# controller11.net
KiCad netlist of a schematic drawn in EAGLE
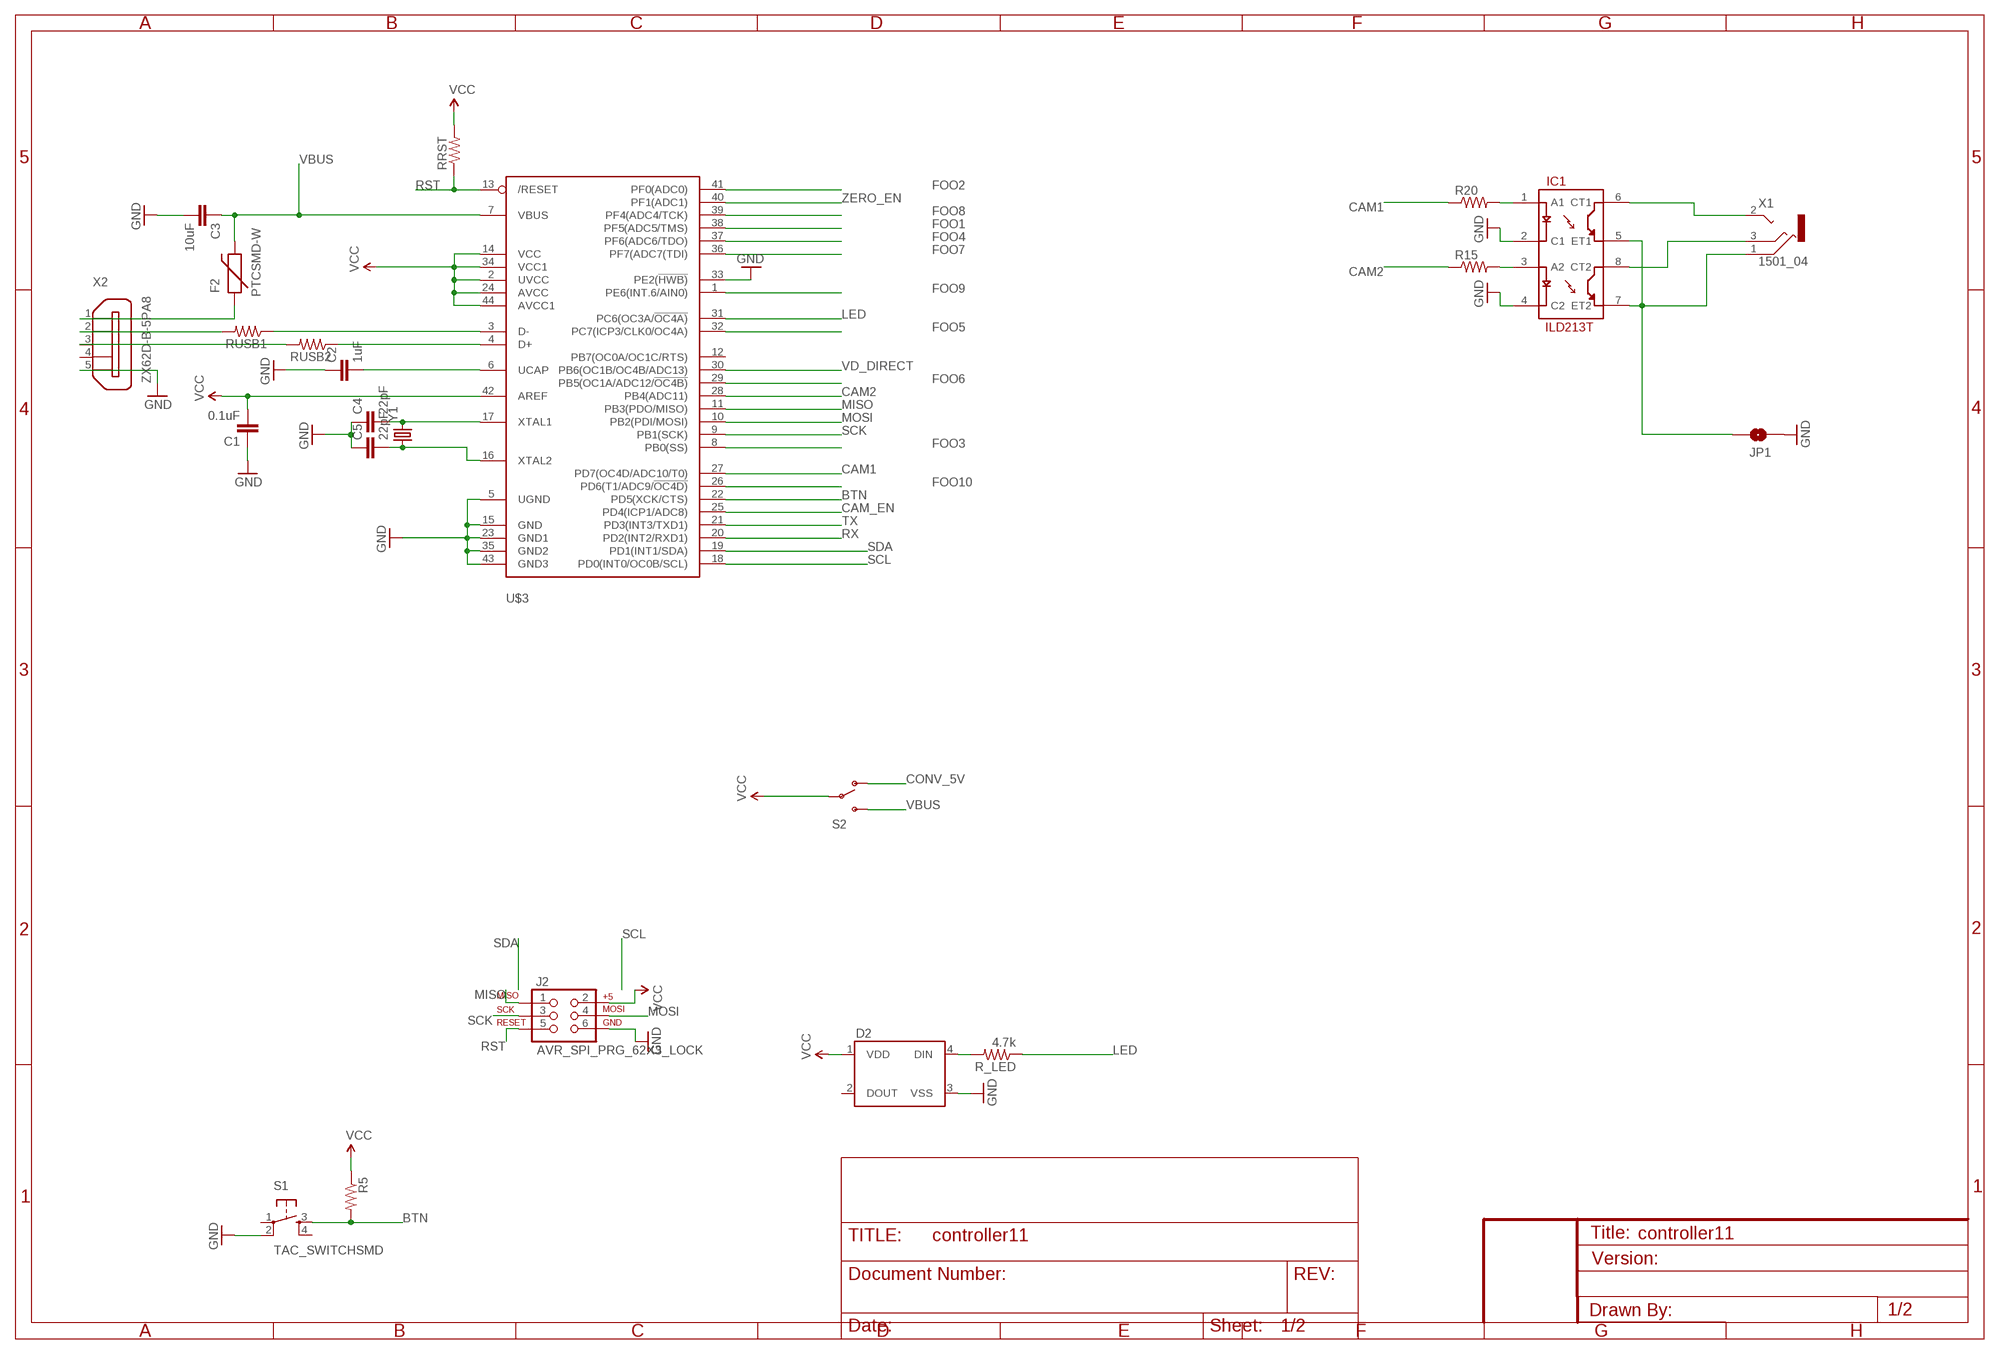
[diagram p0: schematic, sheet 1]
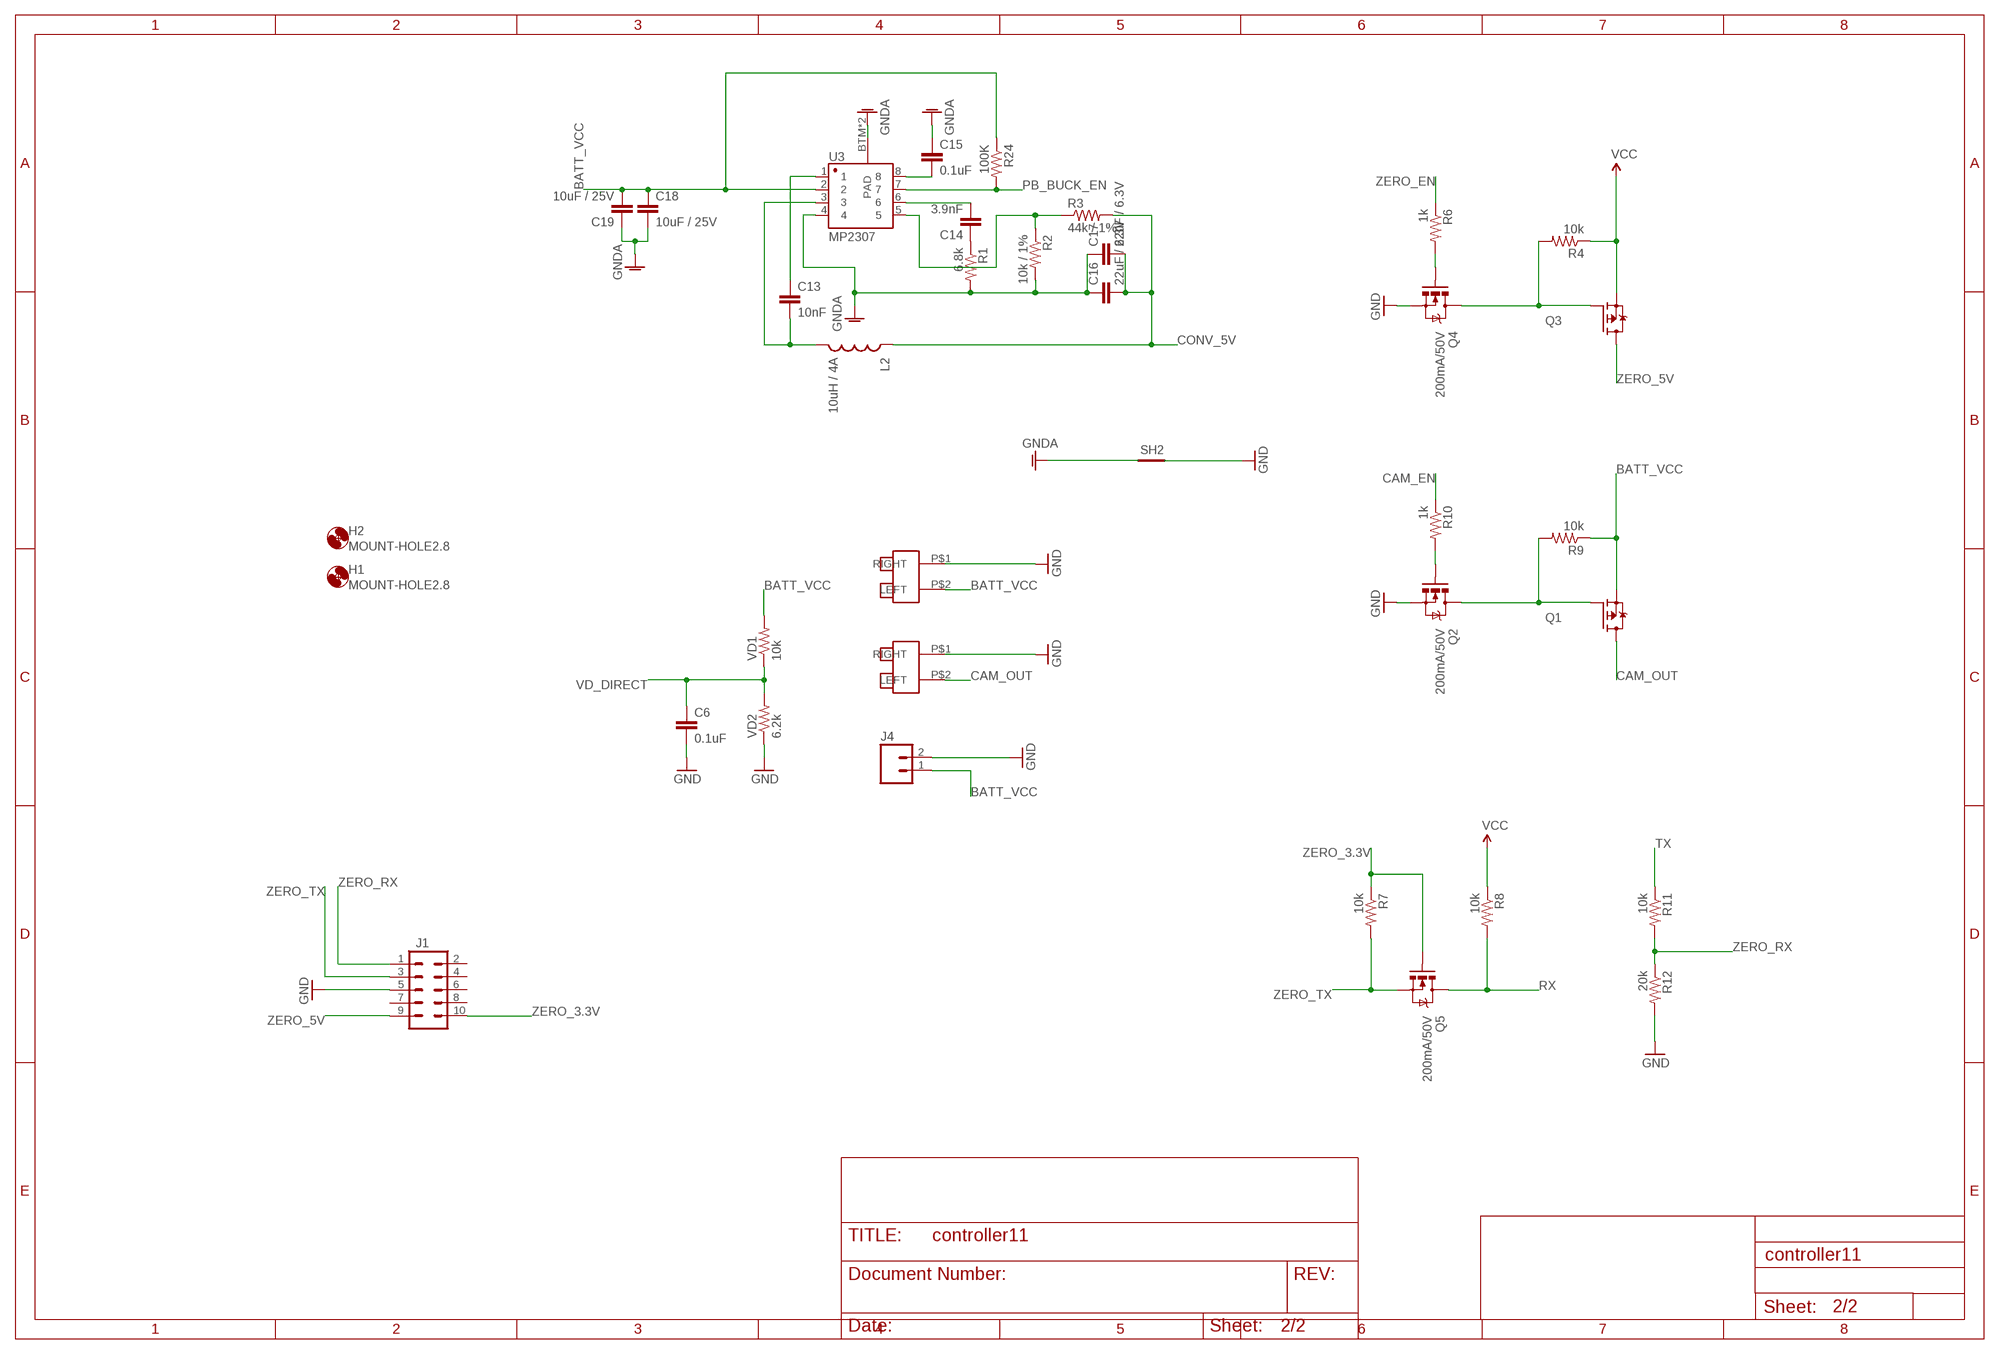
[diagram p1: schematic, sheet 2]

(export (version "E")
  (design (tool "Eeschema 10.0.6"))
  (components
    (comp (ref "C1")
      (value "0.1uF")
      (footprint "eagle-import:1206")
      (libsource (lib "eagle-import") (part "CAP1206"))
    )
    (comp (ref "C2")
      (value "1uF")
      (footprint "eagle-import:1206")
      (libsource (lib "eagle-import") (part "CAP1206"))
    )
    (comp (ref "C3")
      (value "10uF")
      (footprint "eagle-import:1206")
      (libsource (lib "eagle-import") (part "SparkFun-Passives_CAP1206"))
    )
    (comp (ref "C4")
      (value "22pF")
      (footprint "eagle-import:1206")
      (libsource (lib "eagle-import") (part "SparkFun-Passives_CAP1206"))
    )
    (comp (ref "C5")
      (value "22pF")
      (footprint "eagle-import:1206")
      (libsource (lib "eagle-import") (part "SparkFun-Passives_CAP1206"))
    )
    (comp (ref "D2")
      (value "WS2812B")
      (footprint "eagle-import:WS2812B")
      (libsource (lib "eagle-import") (part "WS2812B"))
    )
    (comp (ref "F2")
      (value "PTCSMD-W")
      (footprint "eagle-import:PTC-1206-WIDE")
      (libsource (lib "eagle-import") (part "PTCSMD-W"))
    )
    (comp (ref "IC1")
      (value "ILD213T")
      (footprint "eagle-import:SO08")
      (libsource (lib "eagle-import") (part "ILD213T"))
    )
    (comp (ref "J2")
      (value "AVR_SPI_PRG_62X3_LOCK")
      (footprint "eagle-import:2X3_LOCK")
      (libsource (lib "eagle-import") (part "AVR_SPI_PRG_62X3_LOCK"))
    )
    (comp (ref "JP1")
      (value "JUMPER-PAD-2-NOYES_SILK")
      (footprint "eagle-import:PAD-JUMPER-2-NO_YES_SILK")
      (libsource (lib "eagle-import") (part "JUMPER-PAD-2-NOYES_SILK"))
    )
    (comp (ref "R5")
      (value "RESISTOR1206")
      (footprint "eagle-import:1206")
      (libsource (lib "eagle-import") (part "RESISTOR1206"))
    )
    (comp (ref "R15")
      (value "RESISTOR1206")
      (footprint "eagle-import:1206")
      (libsource (lib "eagle-import") (part "RESISTOR1206"))
    )
    (comp (ref "R20")
      (value "RESISTOR1206")
      (footprint "eagle-import:1206")
      (libsource (lib "eagle-import") (part "RESISTOR1206"))
    )
    (comp (ref "RRST")
      (value "RESISTOR1206")
      (footprint "eagle-import:1206")
      (libsource (lib "eagle-import") (part "RESISTOR1206"))
    )
    (comp (ref "RUSB1")
      (value "RESISTOR1206")
      (footprint "eagle-import:1206")
      (libsource (lib "eagle-import") (part "RESISTOR1206"))
    )
    (comp (ref "RUSB2")
      (value "RESISTOR1206")
      (footprint "eagle-import:1206")
      (libsource (lib "eagle-import") (part "RESISTOR1206"))
    )
    (comp (ref "R_LED")
      (value "4.7k")
      (footprint "eagle-import:1206")
      (libsource (lib "eagle-import") (part "SparkFun-Resistors_RESISTOR1206"))
    )
    (comp (ref "S1")
      (value "TAC_SWITCHSMD")
      (footprint "eagle-import:TACTILE-SWITCH-SMD")
      (libsource (lib "eagle-import") (part "TAC_SWITCHSMD"))
    )
    (comp (ref "S2")
      (value "SWITCH-SPDTSMD2")
      (footprint "eagle-import:SWITCH-SPDT-SMD")
      (libsource (lib "eagle-import") (part "SWITCH-SPDTSMD2"))
    )
    (comp (ref "U$3")
      (value "ATMEGA32U4-AU")
      (footprint "eagle-import:TQFP44")
      (libsource (lib "eagle-import") (part "ATMEGA32U4-AU"))
    )
    (comp (ref "X1")
      (value "1501_04")
      (footprint "eagle-import:1501_05")
      (libsource (lib "eagle-import") (part "1501_04"))
    )
    (comp (ref "X2")
      (value "ZX62D-B-5PA8")
      (footprint "eagle-import:ZX62D-B-5PA8")
      (fields (field (name "MF") "Hirose"))
      (libsource (lib "eagle-import") (part "ZX62D-B-5PA8"))
    )
    (comp (ref "Y1")
      (value "CRYSTALCRYSTAL-SMD-5X3-16MHZ")
      (footprint "eagle-import:CRYSTAL-SMD-5X3")
      (libsource (lib "eagle-import") (part "CRYSTALCRYSTAL-SMD-5X3-16MHZ"))
    )
    (comp (ref "C6")
      (value "0.1uF")
      (footprint "eagle-import:1206")
      (libsource (lib "eagle-import") (part "CAP1206"))
    )
    (comp (ref "C13")
      (value "10nF")
      (footprint "eagle-import:1206")
      (libsource (lib "eagle-import") (part "CAP1206"))
    )
    (comp (ref "C14")
      (value "3.9nF")
      (footprint "eagle-import:1206")
      (libsource (lib "eagle-import") (part "CAP1206"))
    )
    (comp (ref "C15")
      (value "0.1uF")
      (footprint "eagle-import:1206")
      (libsource (lib "eagle-import") (part "CAP1206"))
    )
    (comp (ref "C16")
      (value "22uF / 6.3V")
      (footprint "eagle-import:1210")
      (libsource (lib "eagle-import") (part "CAP1210"))
    )
    (comp (ref "C17")
      (value "22uF / 6.3V")
      (footprint "eagle-import:1210")
      (libsource (lib "eagle-import") (part "CAP1210"))
    )
    (comp (ref "C18")
      (value "10uF / 25V")
      (footprint "eagle-import:1210")
      (libsource (lib "eagle-import") (part "CAP1210"))
    )
    (comp (ref "C19")
      (value "10uF / 25V")
      (footprint "eagle-import:1210")
      (libsource (lib "eagle-import") (part "CAP1210"))
    )
    (comp (ref "H1")
      (value "MOUNT-HOLE2.8")
      (footprint "eagle-import:2,8")
      (libsource (lib "eagle-import") (part "MOUNT-HOLE2.8"))
    )
    (comp (ref "H2")
      (value "MOUNT-HOLE2.8")
      (footprint "eagle-import:2,8")
      (libsource (lib "eagle-import") (part "MOUNT-HOLE2.8"))
    )
    (comp (ref "J1")
      (value "M05X2PTH")
      (footprint "eagle-import:AVR_ICSP")
      (libsource (lib "eagle-import") (part "M05X2PTH"))
    )
    (comp (ref "J4")
      (value "M02LOCK")
      (footprint "eagle-import:1X02_LOCK")
      (libsource (lib "eagle-import") (part "M02LOCK"))
    )
    (comp (ref "L2")
      (value "10uH / 4A")
      (footprint "eagle-import:SRU1038")
      (libsource (lib "eagle-import") (part "INDUCTORSRU1038"))
    )
    (comp (ref "Q1")
      (value "FDD4141TO252")
      (footprint "eagle-import:TO252")
      (libsource (lib "eagle-import") (part "FDD4141TO252"))
    )
    (comp (ref "Q2")
      (value "200mA/50V")
      (footprint "eagle-import:SOT23-3")
      (libsource (lib "eagle-import") (part "MOSFET-NCHANNELBSS138"))
    )
    (comp (ref "Q3")
      (value "FDD4141TO252")
      (footprint "eagle-import:TO252")
      (libsource (lib "eagle-import") (part "FDD4141TO252"))
    )
    (comp (ref "Q4")
      (value "200mA/50V")
      (footprint "eagle-import:SOT23-3")
      (libsource (lib "eagle-import") (part "MOSFET-NCHANNELBSS138"))
    )
    (comp (ref "Q5")
      (value "200mA/50V")
      (footprint "eagle-import:SOT23-3")
      (libsource (lib "eagle-import") (part "MOSFET-NCHANNELBSS138"))
    )
    (comp (ref "R1")
      (value "6.8k")
      (footprint "eagle-import:1206")
      (libsource (lib "eagle-import") (part "SparkFun-Resistors_RESISTOR1206"))
    )
    (comp (ref "R2")
      (value "10k / 1%")
      (footprint "eagle-import:1206")
      (libsource (lib "eagle-import") (part "SparkFun-Resistors_RESISTOR1206"))
    )
    (comp (ref "R3")
      (value "44k / 1%")
      (footprint "eagle-import:1206")
      (libsource (lib "eagle-import") (part "SparkFun-Resistors_RESISTOR1206"))
    )
    (comp (ref "R4")
      (value "10k")
      (footprint "eagle-import:1206")
      (libsource (lib "eagle-import") (part "SparkFun-Resistors_RESISTOR1206"))
    )
    (comp (ref "R6")
      (value "1k")
      (footprint "eagle-import:1206")
      (libsource (lib "eagle-import") (part "SparkFun-Resistors_RESISTOR1206"))
    )
    (comp (ref "R7")
      (value "10k")
      (footprint "eagle-import:1206")
      (libsource (lib "eagle-import") (part "SparkFun-Resistors_RESISTOR1206"))
    )
    (comp (ref "R8")
      (value "10k")
      (footprint "eagle-import:1206")
      (libsource (lib "eagle-import") (part "SparkFun-Resistors_RESISTOR1206"))
    )
    (comp (ref "R9")
      (value "10k")
      (footprint "eagle-import:1206")
      (libsource (lib "eagle-import") (part "SparkFun-Resistors_RESISTOR1206"))
    )
    (comp (ref "R10")
      (value "1k")
      (footprint "eagle-import:1206")
      (libsource (lib "eagle-import") (part "SparkFun-Resistors_RESISTOR1206"))
    )
    (comp (ref "R11")
      (value "10k")
      (footprint "eagle-import:1206")
      (libsource (lib "eagle-import") (part "SparkFun-Resistors_RESISTOR1206"))
    )
    (comp (ref "R12")
      (value "20k")
      (footprint "eagle-import:1206")
      (libsource (lib "eagle-import") (part "SparkFun-Resistors_RESISTOR1206"))
    )
    (comp (ref "R24")
      (value "100K")
      (footprint "eagle-import:1206")
      (libsource (lib "eagle-import") (part "SparkFun-Resistors_RESISTOR1206"))
    )
    (comp (ref "SH2")
      (value "SHORT-HT5")
      (footprint "eagle-import:SHORT_TOP-50")
      (libsource (lib "eagle-import") (part "SHORT-HT5"))
    )
    (comp (ref "U$4")
      (value "NANOFIT2")
      (footprint "eagle-import:NANOFIT2")
      (libsource (lib "eagle-import") (part "NANOFIT2"))
    )
    (comp (ref "U$5")
      (value "NANOFIT2")
      (footprint "eagle-import:NANOFIT2")
      (libsource (lib "eagle-import") (part "NANOFIT2"))
    )
    (comp (ref "U3")
      (value "MP2307")
      (footprint "eagle-import:SO08")
      (libsource (lib "eagle-import") (part "GENERIC-SOIC8MSGEQ7N-FILTER"))
    )
    (comp (ref "VD1")
      (value "10k")
      (footprint "eagle-import:1206")
      (libsource (lib "eagle-import") (part "RESISTOR1206"))
    )
    (comp (ref "VD2")
      (value "6.2k")
      (footprint "eagle-import:1206")
      (libsource (lib "eagle-import") (part "RESISTOR1206"))
    )
  )
  (nets
    (net (code "1") (name "BATT_VCC") (class "Default")
      (node (ref "C18") (pin "1") (pinfunction "1_1") (pintype "passive"))
      (node (ref "C19") (pin "2") (pinfunction "2_2") (pintype "passive"))
      (node (ref "J4") (pin "1") (pinfunction "1_1") (pintype "passive"))
      (node (ref "Q1") (pin "2") (pinfunction "S_2") (pintype "passive"))
      (node (ref "R24") (pin "1") (pinfunction "1_1") (pintype "passive"))
      (node (ref "R9") (pin "1") (pinfunction "1_1") (pintype "passive"))
      (node (ref "U$4") (pin "P$2") (pinfunction "LEFT_P$2") (pintype "bidirectional"))
      (node (ref "U3") (pin "2") (pinfunction "2_2") (pintype "bidirectional"))
      (node (ref "VD1") (pin "2") (pinfunction "2_2") (pintype "passive"))
    )
    (net (code "2") (name "BTN") (class "Default")
      (node (ref "R5") (pin "2") (pinfunction "2_2") (pintype "passive"))
      (node (ref "S1") (pin "3") (pinfunction "3_3") (pintype "passive"))
      (node (ref "U$3") (pin "22") (pinfunction "PD5(XCK/CTS)_22") (pintype "bidirectional"))
    )
    (net (code "3") (name "CAM1") (class "Default")
      (node (ref "R20") (pin "1") (pinfunction "1_1") (pintype "passive"))
      (node (ref "U$3") (pin "27") (pinfunction "PD7(OC4D/ADC10/T0)_27") (pintype "bidirectional"))
    )
    (net (code "4") (name "CAM2") (class "Default")
      (node (ref "R15") (pin "1") (pinfunction "1_1") (pintype "passive"))
      (node (ref "U$3") (pin "28") (pinfunction "PB4(ADC11)_28") (pintype "bidirectional"))
    )
    (net (code "5") (name "CAM_EN") (class "Default")
      (node (ref "R10") (pin "1") (pinfunction "1_1") (pintype "passive"))
      (node (ref "U$3") (pin "25") (pinfunction "PD4(ICP1/ADC8)_25") (pintype "bidirectional"))
    )
    (net (code "6") (name "CAM_OUT") (class "Default")
      (node (ref "Q1") (pin "3") (pinfunction "D_3") (pintype "passive"))
      (node (ref "U$5") (pin "P$2") (pinfunction "LEFT_P$2") (pintype "bidirectional"))
    )
    (net (code "7") (name "CONV_5V") (class "Default")
      (node (ref "C16") (pin "2") (pinfunction "2_2") (pintype "passive"))
      (node (ref "C17") (pin "2") (pinfunction "2_2") (pintype "passive"))
      (node (ref "L2") (pin "1") (pinfunction "1_1") (pintype "passive"))
      (node (ref "R3") (pin "2") (pinfunction "2_2") (pintype "passive"))
      (node (ref "S2") (pin "1") (pinfunction "O_1") (pintype "passive"))
    )
    (net (code "8") (name "FOO1") (class "Default")
      (node (ref "U$3") (pin "38") (pinfunction "PF5(ADC5/TMS)_38") (pintype "bidirectional"))
    )
    (net (code "9") (name "FOO2") (class "Default")
      (node (ref "U$3") (pin "41") (pinfunction "PF0(ADC0)_41") (pintype "bidirectional"))
    )
    (net (code "10") (name "FOO3") (class "Default")
      (node (ref "U$3") (pin "8") (pinfunction "PB0(SS)_8") (pintype "bidirectional"))
    )
    (net (code "11") (name "FOO4") (class "Default")
      (node (ref "U$3") (pin "37") (pinfunction "PF6(ADC6/TDO)_37") (pintype "bidirectional"))
    )
    (net (code "12") (name "FOO5") (class "Default")
      (node (ref "U$3") (pin "32") (pinfunction "PC7(ICP3/CLK0/OC4A)_32") (pintype "bidirectional"))
    )
    (net (code "13") (name "FOO6") (class "Default")
      (node (ref "U$3") (pin "29") (pinfunction "PB5(OC1A/ADC12/~{OC4B})_29") (pintype "bidirectional"))
    )
    (net (code "14") (name "FOO7") (class "Default")
      (node (ref "U$3") (pin "36") (pinfunction "PF7(ADC7(TDI)_36") (pintype "bidirectional"))
    )
    (net (code "15") (name "FOO8") (class "Default")
      (node (ref "U$3") (pin "39") (pinfunction "PF4(ADC4/TCK)_39") (pintype "bidirectional"))
    )
    (net (code "16") (name "FOO9") (class "Default")
      (node (ref "U$3") (pin "1") (pinfunction "PE6(INT.6/AIN0)_1") (pintype "bidirectional"))
    )
    (net (code "17") (name "FOO10") (class "Default")
      (node (ref "U$3") (pin "26") (pinfunction "PD6(T1/ADC9/~{OC4D})_26") (pintype "bidirectional"))
    )
    (net (code "18") (name "GND") (class "Default")
      (node (ref "C1") (pin "1") (pinfunction "1_1") (pintype "passive"))
      (node (ref "C2") (pin "1") (pinfunction "1_1") (pintype "passive"))
      (node (ref "C3") (pin "2") (pinfunction "2_2") (pintype "passive"))
      (node (ref "C4") (pin "1") (pinfunction "1_1") (pintype "passive"))
      (node (ref "C5") (pin "1") (pinfunction "1_1") (pintype "passive"))
      (node (ref "C6") (pin "2") (pinfunction "2_2") (pintype "passive"))
      (node (ref "D2") (pin "3") (pinfunction "VSS_3") (pintype "power_in"))
      (node (ref "IC1") (pin "2") (pinfunction "C1_2") (pintype "bidirectional"))
      (node (ref "IC1") (pin "4") (pinfunction "C2_4") (pintype "bidirectional"))
      (node (ref "J1") (pin "5") (pinfunction "5_5") (pintype "passive"))
      (node (ref "J2") (pin "6") (pinfunction "6_6") (pintype "passive"))
      (node (ref "J4") (pin "2") (pinfunction "2_2") (pintype "passive"))
      (node (ref "JP1") (pin "1") (pinfunction "1_1") (pintype "passive"))
      (node (ref "Q2") (pin "2") (pinfunction "S_2") (pintype "passive"))
      (node (ref "Q4") (pin "2") (pinfunction "S_2") (pintype "passive"))
      (node (ref "R12") (pin "2") (pinfunction "2_2") (pintype "passive"))
      (node (ref "S1") (pin "2") (pinfunction "2_2") (pintype "passive"))
      (node (ref "SH2") (pin "2") (pinfunction "P$2_2") (pintype "bidirectional"))
      (node (ref "U$3") (pin "15") (pinfunction "GND_15") (pintype "bidirectional"))
      (node (ref "U$3") (pin "23") (pinfunction "GND1_23") (pintype "bidirectional"))
      (node (ref "U$3") (pin "33") (pinfunction "PE2(~{HWB})_33") (pintype "bidirectional"))
      (node (ref "U$3") (pin "35") (pinfunction "GND2_35") (pintype "bidirectional"))
      (node (ref "U$3") (pin "43") (pinfunction "GND3_43") (pintype "bidirectional"))
      (node (ref "U$3") (pin "5") (pinfunction "UGND_5") (pintype "bidirectional"))
      (node (ref "U$4") (pin "P$1") (pinfunction "RIGHT_P$1") (pintype "bidirectional"))
      (node (ref "U$5") (pin "P$1") (pinfunction "RIGHT_P$1") (pintype "bidirectional"))
      (node (ref "VD2") (pin "1") (pinfunction "1_1") (pintype "passive"))
      (node (ref "X2") (pin "5") (pinfunction "5_5") (pintype "passive"))
    )
    (net (code "19") (name "GNDA") (class "Default")
      (node (ref "C15") (pin "1") (pinfunction "1_1") (pintype "passive"))
      (node (ref "C16") (pin "1") (pinfunction "1_1") (pintype "passive"))
      (node (ref "C17") (pin "1") (pinfunction "1_1") (pintype "passive"))
      (node (ref "C18") (pin "2") (pinfunction "2_2") (pintype "passive"))
      (node (ref "C19") (pin "1") (pinfunction "1_1") (pintype "passive"))
      (node (ref "R1") (pin "2") (pinfunction "2_2") (pintype "passive"))
      (node (ref "R2") (pin "2") (pinfunction "2_2") (pintype "passive"))
      (node (ref "SH2") (pin "1") (pinfunction "P$1_1") (pintype "bidirectional"))
      (node (ref "U3") (pin "4") (pinfunction "4_4") (pintype "bidirectional"))
      (node (ref "U3") (pin "BTM") (pinfunction "PAD_BTM") (pintype "bidirectional"))
      (node (ref "U3") (pin "P$1") (pinfunction "PAD_P$1") (pintype "bidirectional"))
    )
    (net (code "20") (name "LED") (class "Default")
      (node (ref "R_LED") (pin "1") (pinfunction "1_1") (pintype "passive"))
      (node (ref "U$3") (pin "31") (pinfunction "PC6(OC3A/~{OC4A})_31") (pintype "bidirectional"))
    )
    (net (code "21") (name "MISO") (class "Default")
      (node (ref "J2") (pin "1") (pinfunction "1_1") (pintype "passive"))
      (node (ref "U$3") (pin "11") (pinfunction "PB3(PDO/MISO)_11") (pintype "bidirectional"))
    )
    (net (code "22") (name "MOSI") (class "Default")
      (node (ref "J2") (pin "4") (pinfunction "4_4") (pintype "passive"))
      (node (ref "U$3") (pin "10") (pinfunction "PB2(PDI/MOSI)_10") (pintype "bidirectional"))
    )
    (net (code "23") (name "Net-(C13-Pad1)") (class "Default")
      (node (ref "C13") (pin "1") (pinfunction "1_1") (pintype "passive"))
      (node (ref "U3") (pin "1") (pinfunction "1_1") (pintype "bidirectional"))
    )
    (net (code "24") (name "Net-(C13-Pad2)") (class "Default")
      (node (ref "C13") (pin "2") (pinfunction "2_2") (pintype "passive"))
      (node (ref "L2") (pin "2") (pinfunction "2_2") (pintype "passive"))
      (node (ref "U3") (pin "3") (pinfunction "3_3") (pintype "bidirectional"))
    )
    (net (code "25") (name "Net-(C14-Pad1)") (class "Default")
      (node (ref "C14") (pin "1") (pinfunction "1_1") (pintype "passive"))
      (node (ref "R1") (pin "1") (pinfunction "1_1") (pintype "passive"))
    )
    (net (code "26") (name "Net-(C14-Pad2)") (class "Default")
      (node (ref "C14") (pin "2") (pinfunction "2_2") (pintype "passive"))
      (node (ref "U3") (pin "6") (pinfunction "6_6") (pintype "bidirectional"))
    )
    (net (code "27") (name "Net-(C15-Pad2)") (class "Default")
      (node (ref "C15") (pin "2") (pinfunction "2_2") (pintype "passive"))
      (node (ref "U3") (pin "8") (pinfunction "8_8") (pintype "bidirectional"))
    )
    (net (code "28") (name "Net-(D2-DIN)") (class "Default")
      (node (ref "D2") (pin "4") (pinfunction "DIN_4") (pintype "input"))
      (node (ref "R_LED") (pin "2") (pinfunction "2_2") (pintype "passive"))
    )
    (net (code "29") (name "Net-(F2-Pad1)") (class "Default")
      (node (ref "F2") (pin "1") (pinfunction "1_1") (pintype "bidirectional"))
      (node (ref "X2") (pin "1") (pinfunction "1_1") (pintype "passive"))
    )
    (net (code "30") (name "Net-(IC1-A1)") (class "Default")
      (node (ref "IC1") (pin "1") (pinfunction "A1_1") (pintype "bidirectional"))
      (node (ref "R20") (pin "2") (pinfunction "2_2") (pintype "passive"))
    )
    (net (code "31") (name "Net-(IC1-A2)") (class "Default")
      (node (ref "IC1") (pin "3") (pinfunction "A2_3") (pintype "bidirectional"))
      (node (ref "R15") (pin "2") (pinfunction "2_2") (pintype "passive"))
    )
    (net (code "32") (name "Net-(IC1-CT1)") (class "Default")
      (node (ref "IC1") (pin "6") (pinfunction "CT1_6") (pintype "bidirectional"))
      (node (ref "X1") (pin "2") (pinfunction "2_2") (pintype "passive"))
    )
    (net (code "33") (name "Net-(IC1-CT2)") (class "Default")
      (node (ref "IC1") (pin "8") (pinfunction "CT2_8") (pintype "bidirectional"))
      (node (ref "X1") (pin "3") (pinfunction "3_3") (pintype "passive"))
    )
    (net (code "34") (name "Net-(IC1-ET1)") (class "Default")
      (node (ref "IC1") (pin "5") (pinfunction "ET1_5") (pintype "bidirectional"))
      (node (ref "IC1") (pin "7") (pinfunction "ET2_7") (pintype "bidirectional"))
      (node (ref "JP1") (pin "2") (pinfunction "2_2") (pintype "passive"))
      (node (ref "X1") (pin "1") (pinfunction "1_1") (pintype "passive"))
    )
    (net (code "35") (name "Net-(Q1-G)") (class "Default")
      (node (ref "Q1") (pin "1") (pinfunction "G_1") (pintype "passive"))
      (node (ref "Q2") (pin "3") (pinfunction "D_3") (pintype "passive"))
      (node (ref "R9") (pin "2") (pinfunction "2_2") (pintype "passive"))
    )
    (net (code "36") (name "Net-(Q2-G)") (class "Default")
      (node (ref "Q2") (pin "1") (pinfunction "G_1") (pintype "passive"))
      (node (ref "R10") (pin "2") (pinfunction "2_2") (pintype "passive"))
    )
    (net (code "37") (name "Net-(Q3-G)") (class "Default")
      (node (ref "Q3") (pin "1") (pinfunction "G_1") (pintype "passive"))
      (node (ref "Q4") (pin "3") (pinfunction "D_3") (pintype "passive"))
      (node (ref "R4") (pin "2") (pinfunction "2_2") (pintype "passive"))
    )
    (net (code "38") (name "Net-(Q4-G)") (class "Default")
      (node (ref "Q4") (pin "1") (pinfunction "G_1") (pintype "passive"))
      (node (ref "R6") (pin "2") (pinfunction "2_2") (pintype "passive"))
    )
    (net (code "39") (name "Net-(R2-Pad1)") (class "Default")
      (node (ref "R2") (pin "1") (pinfunction "1_1") (pintype "passive"))
      (node (ref "R3") (pin "1") (pinfunction "1_1") (pintype "passive"))
      (node (ref "U3") (pin "5") (pinfunction "5_5") (pintype "bidirectional"))
    )
    (net (code "40") (name "Net-(RUSB1-Pad2)") (class "Default")
      (node (ref "RUSB1") (pin "2") (pinfunction "2_2") (pintype "passive"))
      (node (ref "X2") (pin "2") (pinfunction "2_2") (pintype "passive"))
    )
    (net (code "41") (name "Net-(RUSB2-Pad2)") (class "Default")
      (node (ref "RUSB2") (pin "2") (pinfunction "2_2") (pintype "passive"))
      (node (ref "X2") (pin "3") (pinfunction "3_3") (pintype "passive"))
    )
    (net (code "42") (name "Net-(U$3-D+)") (class "Default")
      (node (ref "RUSB2") (pin "1") (pinfunction "1_1") (pintype "passive"))
      (node (ref "U$3") (pin "4") (pinfunction "D+_4") (pintype "bidirectional"))
    )
    (net (code "43") (name "Net-(U$3-D-)") (class "Default")
      (node (ref "RUSB1") (pin "1") (pinfunction "1_1") (pintype "passive"))
      (node (ref "U$3") (pin "3") (pinfunction "D-_3") (pintype "bidirectional"))
    )
    (net (code "44") (name "Net-(U$3-UCAP)") (class "Default")
      (node (ref "C2") (pin "2") (pinfunction "2_2") (pintype "passive"))
      (node (ref "U$3") (pin "6") (pinfunction "UCAP_6") (pintype "bidirectional"))
    )
    (net (code "45") (name "Net-(U$3-XTAL1)") (class "Default")
      (node (ref "C4") (pin "2") (pinfunction "2_2") (pintype "passive"))
      (node (ref "U$3") (pin "17") (pinfunction "XTAL1_17") (pintype "bidirectional"))
      (node (ref "Y1") (pin "3") (pinfunction "2_3") (pintype "passive"))
    )
    (net (code "46") (name "Net-(U$3-XTAL2)") (class "Default")
      (node (ref "C5") (pin "2") (pinfunction "2_2") (pintype "passive"))
      (node (ref "U$3") (pin "16") (pinfunction "XTAL2_16") (pintype "bidirectional"))
      (node (ref "Y1") (pin "1") (pinfunction "1_1") (pintype "passive"))
    )
    (net (code "47") (name "PB_BUCK_EN") (class "Default")
      (node (ref "R24") (pin "2") (pinfunction "2_2") (pintype "passive"))
      (node (ref "U3") (pin "7") (pinfunction "7_7") (pintype "bidirectional"))
    )
    (net (code "48") (name "RST") (class "Default")
      (node (ref "J2") (pin "5") (pinfunction "5_5") (pintype "passive"))
      (node (ref "RRST") (pin "1") (pinfunction "1_1") (pintype "passive"))
      (node (ref "U$3") (pin "13") (pinfunction "/RESET_13") (pintype "bidirectional"))
    )
    (net (code "49") (name "RX") (class "Default")
      (node (ref "Q5") (pin "3") (pinfunction "D_3") (pintype "passive"))
      (node (ref "R8") (pin "2") (pinfunction "2_2") (pintype "passive"))
      (node (ref "U$3") (pin "20") (pinfunction "PD2(INT2/RXD1)_20") (pintype "bidirectional"))
    )
    (net (code "50") (name "SCK") (class "Default")
      (node (ref "J2") (pin "3") (pinfunction "3_3") (pintype "passive"))
      (node (ref "U$3") (pin "9") (pinfunction "PB1(SCK)_9") (pintype "bidirectional"))
    )
    (net (code "51") (name "SCL") (class "Default")
      (node (ref "U$3") (pin "18") (pinfunction "PD0(INT0/OC0B/SCL)_18") (pintype "bidirectional"))
    )
    (net (code "52") (name "SDA") (class "Default")
      (node (ref "U$3") (pin "19") (pinfunction "PD1(INT1/SDA)_19") (pintype "bidirectional"))
    )
    (net (code "53") (name "TX") (class "Default")
      (node (ref "R11") (pin "1") (pinfunction "1_1") (pintype "passive"))
      (node (ref "U$3") (pin "21") (pinfunction "PD3(INT3/TXD1)_21") (pintype "bidirectional"))
    )
    (net (code "54") (name "VBUS") (class "Default")
      (node (ref "C3") (pin "1") (pinfunction "1_1") (pintype "passive"))
      (node (ref "F2") (pin "2") (pinfunction "2_2") (pintype "bidirectional"))
      (node (ref "S2") (pin "3") (pinfunction "S_3") (pintype "passive"))
      (node (ref "U$3") (pin "7") (pinfunction "VBUS_7") (pintype "bidirectional"))
    )
    (net (code "55") (name "VCC") (class "Default")
      (node (ref "C1") (pin "2") (pinfunction "2_2") (pintype "passive"))
      (node (ref "D2") (pin "1") (pinfunction "VDD_1") (pintype "power_in"))
      (node (ref "J2") (pin "2") (pinfunction "2_2") (pintype "passive"))
      (node (ref "Q3") (pin "2") (pinfunction "S_2") (pintype "passive"))
      (node (ref "R4") (pin "1") (pinfunction "1_1") (pintype "passive"))
      (node (ref "R5") (pin "1") (pinfunction "1_1") (pintype "passive"))
      (node (ref "R8") (pin "1") (pinfunction "1_1") (pintype "passive"))
      (node (ref "RRST") (pin "2") (pinfunction "2_2") (pintype "passive"))
      (node (ref "S2") (pin "2") (pinfunction "P_2") (pintype "passive"))
      (node (ref "U$3") (pin "14") (pinfunction "VCC_14") (pintype "bidirectional"))
      (node (ref "U$3") (pin "2") (pinfunction "UVCC_2") (pintype "bidirectional"))
      (node (ref "U$3") (pin "24") (pinfunction "AVCC_24") (pintype "bidirectional"))
      (node (ref "U$3") (pin "34") (pinfunction "VCC1_34") (pintype "bidirectional"))
      (node (ref "U$3") (pin "42") (pinfunction "AREF_42") (pintype "bidirectional"))
      (node (ref "U$3") (pin "44") (pinfunction "AVCC1_44") (pintype "bidirectional"))
    )
    (net (code "56") (name "VD_DIRECT") (class "Default")
      (node (ref "C6") (pin "1") (pinfunction "1_1") (pintype "passive"))
      (node (ref "U$3") (pin "30") (pinfunction "PB6(OC1B/OC4B/ADC13)_30") (pintype "bidirectional"))
      (node (ref "VD1") (pin "1") (pinfunction "1_1") (pintype "passive"))
      (node (ref "VD2") (pin "2") (pinfunction "2_2") (pintype "passive"))
    )
    (net (code "57") (name "ZERO_3.3V") (class "Default")
      (node (ref "J1") (pin "10") (pinfunction "10_10") (pintype "passive"))
      (node (ref "Q5") (pin "1") (pinfunction "G_1") (pintype "passive"))
      (node (ref "R7") (pin "1") (pinfunction "1_1") (pintype "passive"))
    )
    (net (code "58") (name "ZERO_5V") (class "Default")
      (node (ref "J1") (pin "9") (pinfunction "9_9") (pintype "passive"))
      (node (ref "Q3") (pin "3") (pinfunction "D_3") (pintype "passive"))
    )
    (net (code "59") (name "ZERO_EN") (class "Default")
      (node (ref "R6") (pin "1") (pinfunction "1_1") (pintype "passive"))
      (node (ref "U$3") (pin "40") (pinfunction "PF1(ADC1)_40") (pintype "bidirectional"))
    )
    (net (code "60") (name "ZERO_RX") (class "Default")
      (node (ref "J1") (pin "1") (pinfunction "1_1") (pintype "passive"))
      (node (ref "R11") (pin "2") (pinfunction "2_2") (pintype "passive"))
      (node (ref "R12") (pin "1") (pinfunction "1_1") (pintype "passive"))
    )
    (net (code "61") (name "ZERO_TX") (class "Default")
      (node (ref "J1") (pin "3") (pinfunction "3_3") (pintype "passive"))
      (node (ref "Q5") (pin "2") (pinfunction "S_2") (pintype "passive"))
      (node (ref "R7") (pin "2") (pinfunction "2_2") (pintype "passive"))
    )
    (net (code "62") (name "unconnected-(D2-DOUT-Pad2)") (class "Default")
      (node (ref "D2") (pin "2") (pinfunction "DOUT_2") (pintype "output"))
    )
    (net (code "63") (name "unconnected-(J1-Pad2)") (class "Default")
      (node (ref "J1") (pin "2") (pinfunction "2_2") (pintype "passive"))
    )
    (net (code "64") (name "unconnected-(J1-Pad4)") (class "Default")
      (node (ref "J1") (pin "4") (pinfunction "4_4") (pintype "passive"))
    )
    (net (code "65") (name "unconnected-(J1-Pad6)") (class "Default")
      (node (ref "J1") (pin "6") (pinfunction "6_6") (pintype "passive"))
    )
    (net (code "66") (name "unconnected-(J1-Pad7)") (class "Default")
      (node (ref "J1") (pin "7") (pinfunction "7_7") (pintype "passive"))
    )
    (net (code "67") (name "unconnected-(J1-Pad8)") (class "Default")
      (node (ref "J1") (pin "8") (pinfunction "8_8") (pintype "passive"))
    )
    (net (code "68") (name "unconnected-(S1-Pad1)") (class "Default")
      (node (ref "S1") (pin "1") (pinfunction "1_1") (pintype "passive"))
    )
    (net (code "69") (name "unconnected-(S1-Pad4)") (class "Default")
      (node (ref "S1") (pin "4") (pinfunction "4_4") (pintype "passive"))
    )
    (net (code "70") (name "unconnected-(U$3-PB7(OC0A{slash}OC1C{slash}RTS)-Pad12)") (class "Default")
      (node (ref "U$3") (pin "12") (pinfunction "PB7(OC0A/OC1C/RTS)_12") (pintype "bidirectional"))
    )
    (net (code "71") (name "unconnected-(X2-Pad4)") (class "Default")
      (node (ref "X2") (pin "4") (pinfunction "4_4") (pintype "passive"))
    )
  )
)
